# GPSTracker_v1_0.net
KiCad netlist of a schematic drawn in EAGLE
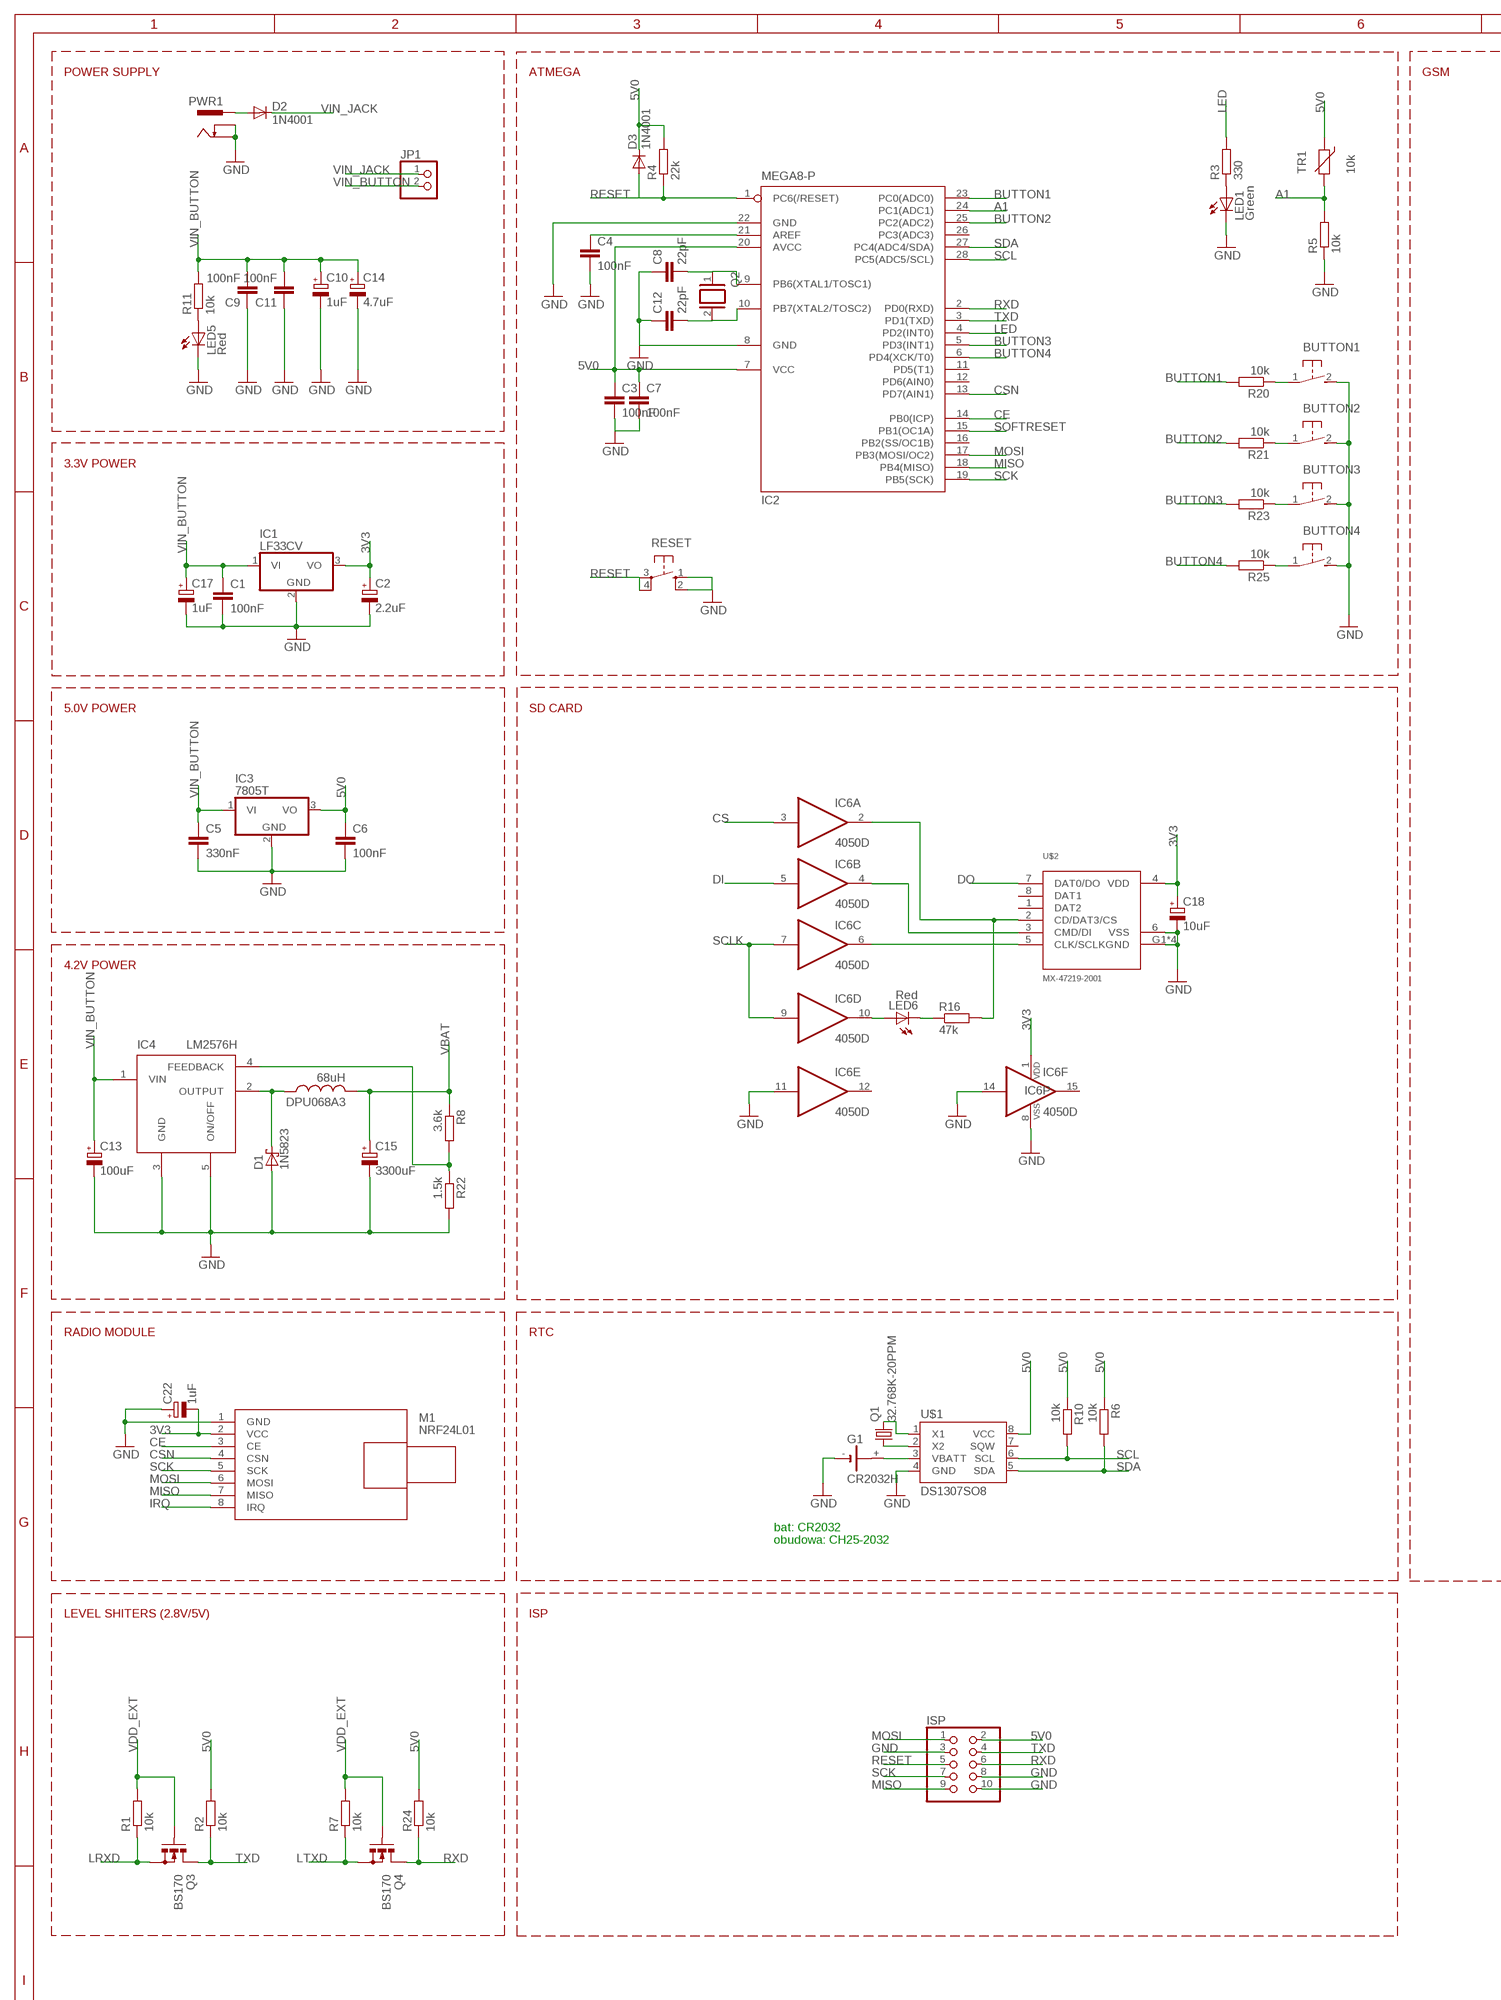
[diagram p0: schematic, sheet 1, part 1 of 2]
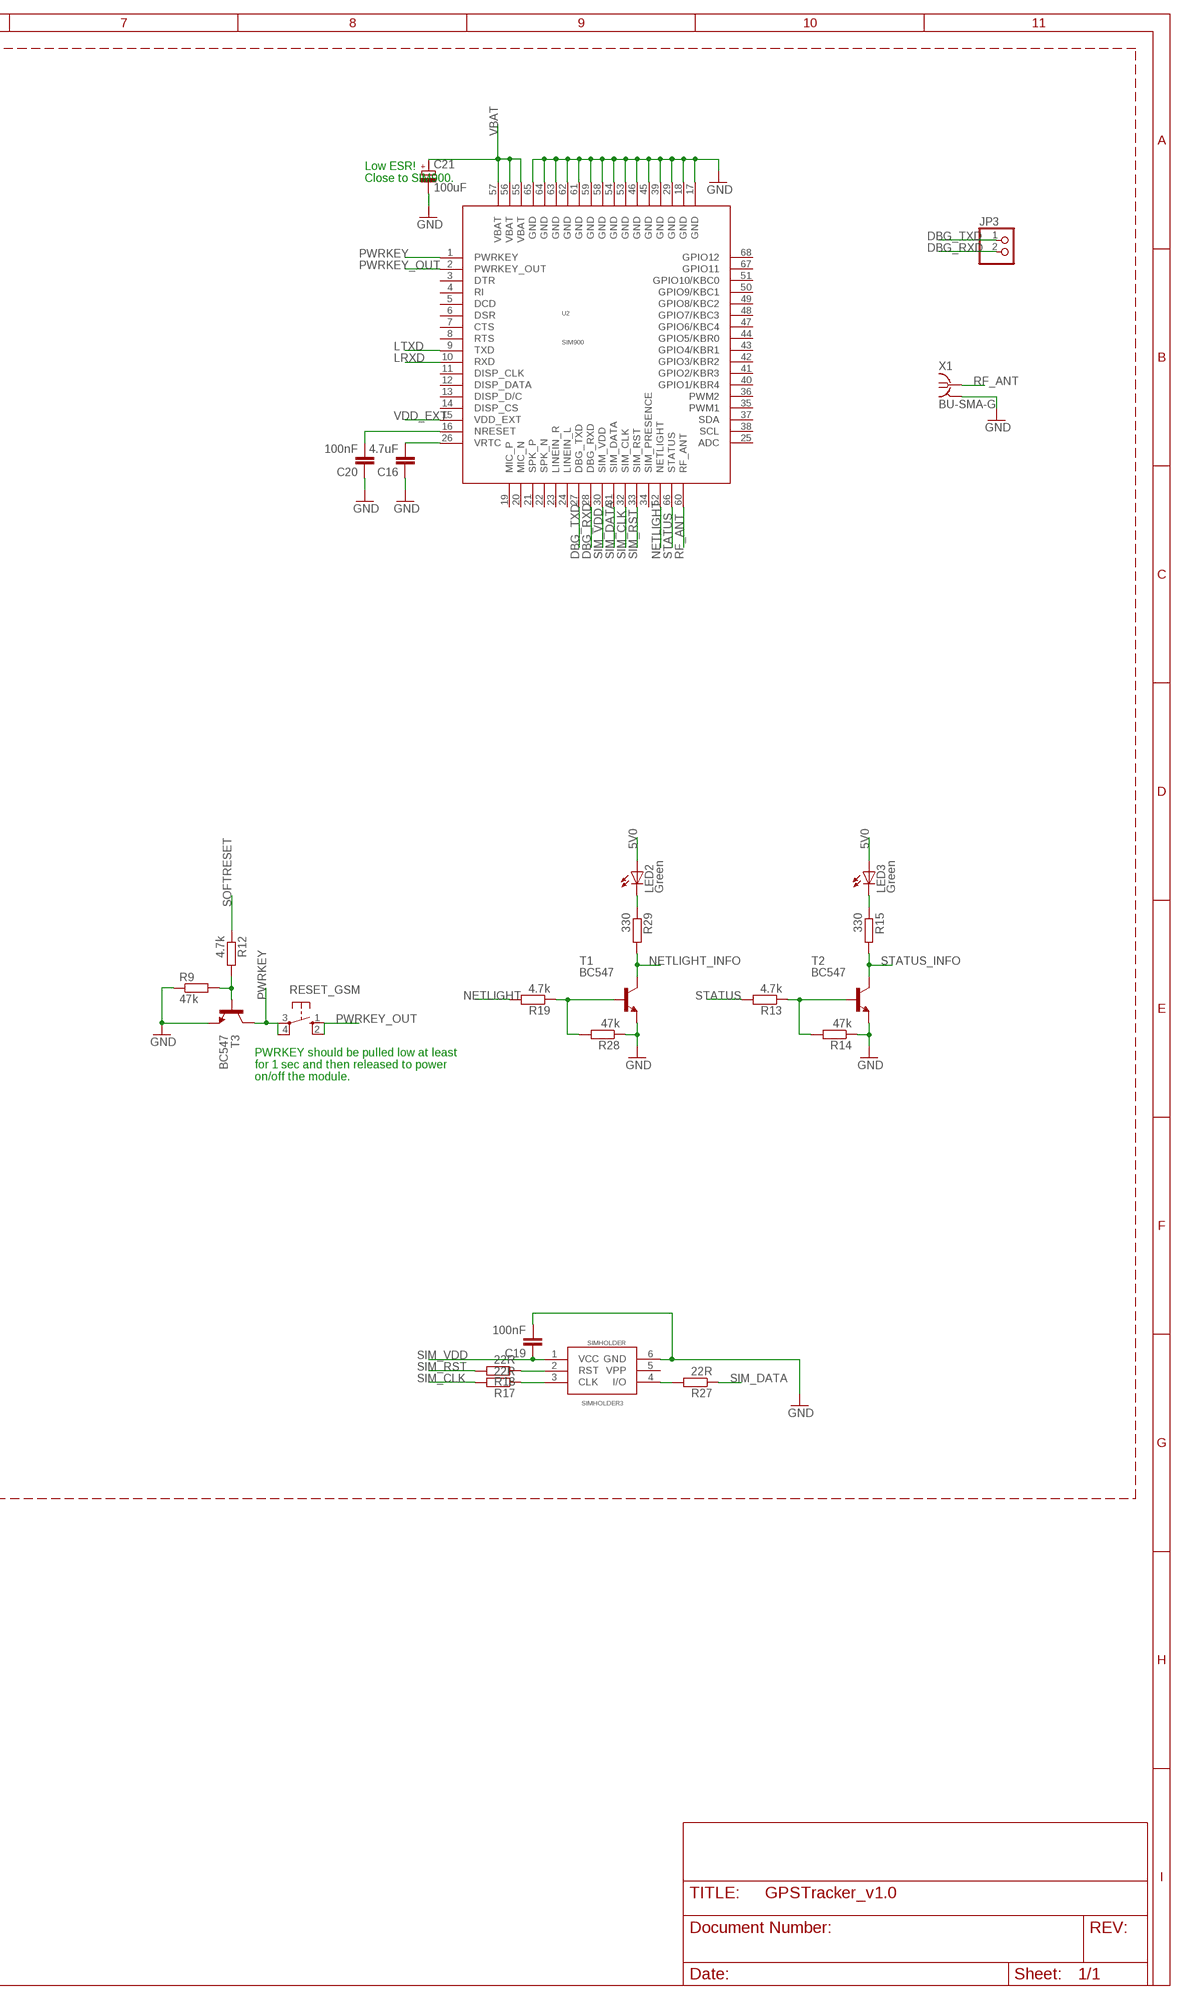
[diagram p1: schematic, sheet 1, part 2 of 2]

(export (version "E")
  (design (tool "Eeschema 10.0.6"))
  (components
    (comp (ref "BUTTON1")
      (value "31-XX")
      (footprint "eagle-import:B3F-31XX")
      (fields (field (name "MPN") "B3F-3100"))
      (libsource (lib "eagle-import") (part "31-XX"))
    )
    (comp (ref "BUTTON2")
      (value "31-XX")
      (footprint "eagle-import:B3F-31XX")
      (fields (field (name "MPN") "B3F-3100"))
      (libsource (lib "eagle-import") (part "31-XX"))
    )
    (comp (ref "BUTTON3")
      (value "31-XX")
      (footprint "eagle-import:B3F-31XX")
      (fields (field (name "MPN") "B3F-3100"))
      (libsource (lib "eagle-import") (part "31-XX"))
    )
    (comp (ref "BUTTON4")
      (value "31-XX")
      (footprint "eagle-import:B3F-31XX")
      (fields (field (name "MPN") "B3F-3100"))
      (libsource (lib "eagle-import") (part "31-XX"))
    )
    (comp (ref "C1")
      (value "100nF")
      (footprint "eagle-import:C025-025X050")
      (libsource (lib "eagle-import") (part "C-EU025-025X050"))
    )
    (comp (ref "C2")
      (value "2.2uF")
      (footprint "eagle-import:E2,5-5")
      (libsource (lib "eagle-import") (part "CPOL-EUE2.5-5"))
    )
    (comp (ref "C3")
      (value "100nF")
      (footprint "eagle-import:C025-025X050")
      (libsource (lib "eagle-import") (part "C-EU025-025X050"))
    )
    (comp (ref "C4")
      (value "100nF")
      (footprint "eagle-import:C025-025X050")
      (libsource (lib "eagle-import") (part "C-EU025-025X050"))
    )
    (comp (ref "C5")
      (value "330nF")
      (footprint "eagle-import:C025-025X050")
      (libsource (lib "eagle-import") (part "C-EU025-025X050"))
    )
    (comp (ref "C6")
      (value "100nF")
      (footprint "eagle-import:C025-025X050")
      (libsource (lib "eagle-import") (part "C-EU025-025X050"))
    )
    (comp (ref "C7")
      (value "100nF")
      (footprint "eagle-import:C025-025X050")
      (libsource (lib "eagle-import") (part "C-EU025-025X050"))
    )
    (comp (ref "C8")
      (value "22pF")
      (footprint "eagle-import:C025-025X050")
      (libsource (lib "eagle-import") (part "C-EU025-025X050"))
    )
    (comp (ref "C9")
      (value "100nF")
      (footprint "eagle-import:C025-025X050")
      (libsource (lib "eagle-import") (part "C-EU025-025X050"))
    )
    (comp (ref "C10")
      (value "1uF")
      (footprint "eagle-import:E2,5-5")
      (libsource (lib "eagle-import") (part "CPOL-EUE2.5-5"))
    )
    (comp (ref "C11")
      (value "100nF")
      (footprint "eagle-import:C025-025X050")
      (libsource (lib "eagle-import") (part "C-EU025-025X050"))
    )
    (comp (ref "C12")
      (value "22pF")
      (footprint "eagle-import:C025-025X050")
      (libsource (lib "eagle-import") (part "C-EU025-025X050"))
    )
    (comp (ref "C13")
      (value "100uF")
      (footprint "eagle-import:E2,5-5")
      (libsource (lib "eagle-import") (part "CPOL-EUE2.5-5"))
    )
    (comp (ref "C14")
      (value "4.7uF")
      (footprint "eagle-import:E2,5-5")
      (libsource (lib "eagle-import") (part "CPOL-EUE2.5-5"))
    )
    (comp (ref "C15")
      (value "3300uF")
      (footprint "eagle-import:E5-13")
      (libsource (lib "eagle-import") (part "CPOL-EUE5-13"))
    )
    (comp (ref "C16")
      (value "4.7uF")
      (footprint "eagle-import:C025-025X050")
      (libsource (lib "eagle-import") (part "C-EU025-025X050"))
    )
    (comp (ref "C17")
      (value "1uF")
      (footprint "eagle-import:E2,5-5")
      (libsource (lib "eagle-import") (part "CPOL-EUE2.5-5"))
    )
    (comp (ref "C18")
      (value "10uF")
      (footprint "eagle-import:E2,5-5")
      (libsource (lib "eagle-import") (part "CPOL-EUE2.5-5"))
    )
    (comp (ref "C19")
      (value "100nF")
      (footprint "eagle-import:C025-025X050")
      (libsource (lib "eagle-import") (part "C-EU025-025X050"))
    )
    (comp (ref "C20")
      (value "100nF")
      (footprint "eagle-import:C025-025X050")
      (libsource (lib "eagle-import") (part "C-EU025-025X050"))
    )
    (comp (ref "C21")
      (value "100uF")
      (footprint "eagle-import:E2,5-5")
      (libsource (lib "eagle-import") (part "CPOL-EUE2.5-5"))
    )
    (comp (ref "C22")
      (value "1uF")
      (footprint "eagle-import:E2,5-5")
      (libsource (lib "eagle-import") (part "CPOL-EUE2.5-5"))
    )
    (comp (ref "D1")
      (value "1N5823")
      (footprint "eagle-import:DO41-7.6")
      (libsource (lib "eagle-import") (part "1N5817-B"))
    )
    (comp (ref "D2")
      (value "1N4001")
      (footprint "eagle-import:DO41-10")
      (libsource (lib "eagle-import") (part "1N4004"))
    )
    (comp (ref "D3")
      (value "1N4001")
      (footprint "eagle-import:DO41-10")
      (libsource (lib "eagle-import") (part "1N4004"))
    )
    (comp (ref "DPU068A3")
      (value "68uH")
      (footprint "eagle-import:TJ4-U1")
      (libsource (lib "eagle-import") (part "L-USTJ4-U1"))
    )
    (comp (ref "G1")
      (value "CR2032H")
      (footprint "eagle-import:CR2032H")
      (libsource (lib "eagle-import") (part "CR2032H"))
    )
    (comp (ref "IC1")
      (value "LF33CV")
      (footprint "eagle-import:TO220H")
      (libsource (lib "eagle-import") (part "78T05"))
    )
    (comp (ref "IC2")
      (value "MEGA8-P")
      (footprint "eagle-import:DIL28-3")
      (libsource (lib "eagle-import") (part "MEGA8-P"))
    )
    (comp (ref "IC3")
      (value "7805T")
      (footprint "eagle-import:TO220H")
      (libsource (lib "eagle-import") (part "78T05"))
    )
    (comp (ref "IC4")
      (value "LM2576H")
      (footprint "eagle-import:TO220-52")
      (libsource (lib "eagle-import") (part "LM2576H"))
    )
    (comp (ref "IC6")
      (value "4050D")
      (footprint "eagle-import:SO16")
      (libsource (lib "eagle-import") (part "4050D"))
    )
    (comp (ref "ISP")
      (value "PINHD-2X5")
      (footprint "eagle-import:2X05")
      (libsource (lib "eagle-import") (part "PINHD-2X5"))
    )
    (comp (ref "JP1")
      (value "PINHD-1X2")
      (footprint "eagle-import:1X02")
      (libsource (lib "eagle-import") (part "PINHD-1X2"))
    )
    (comp (ref "JP3")
      (value "PINHD-1X2")
      (footprint "eagle-import:1X02")
      (libsource (lib "eagle-import") (part "PINHD-1X2"))
    )
    (comp (ref "LED1")
      (value "Green")
      (footprint "eagle-import:LED3MM")
      (libsource (lib "eagle-import") (part "LED3MM"))
    )
    (comp (ref "LED2")
      (value "Green")
      (footprint "eagle-import:LED3MM")
      (libsource (lib "eagle-import") (part "LED3MM"))
    )
    (comp (ref "LED3")
      (value "Green")
      (footprint "eagle-import:LED3MM")
      (libsource (lib "eagle-import") (part "LED3MM"))
    )
    (comp (ref "LED5")
      (value "Red")
      (footprint "eagle-import:LED3MM")
      (libsource (lib "eagle-import") (part "LED3MM"))
    )
    (comp (ref "LED6")
      (value "Red")
      (footprint "eagle-import:LED3MM")
      (libsource (lib "eagle-import") (part "LED3MM"))
    )
    (comp (ref "M1")
      (value "NRF24L01")
      (footprint "eagle-import:WIRELESS-NRD24L01-PA-EXT")
      (libsource (lib "eagle-import") (part "WIRELESS-NRF24L01-PA-EXT"))
    )
    (comp (ref "PWR1")
      (value "PWR-JAKPWR_JACK_UNI_MILLING")
      (footprint "eagle-import:PWR_JACK_UNI_MILLING")
      (libsource (lib "eagle-import") (part "PWR-JAKPWR_JACK_UNI_MILLING"))
    )
    (comp (ref "Q1")
      (value "32.768K-20PPM")
      (footprint "eagle-import:TC26V")
      (libsource (lib "eagle-import") (part "CRYSTALTC26V"))
    )
    (comp (ref "Q2")
      (value "XTAL/S")
      (footprint "eagle-import:QS")
      (libsource (lib "eagle-import") (part "XTAL/S"))
    )
    (comp (ref "Q3")
      (value "BS170")
      (footprint "eagle-import:SOT54E")
      (libsource (lib "eagle-import") (part "BS170"))
    )
    (comp (ref "Q4")
      (value "BS170")
      (footprint "eagle-import:SOT54E")
      (libsource (lib "eagle-import") (part "BS170"))
    )
    (comp (ref "R1")
      (value "10k")
      (footprint "eagle-import:0207_10")
      (libsource (lib "eagle-import") (part "R-EU_0207/10"))
    )
    (comp (ref "R2")
      (value "10k")
      (footprint "eagle-import:0207_10")
      (libsource (lib "eagle-import") (part "R-EU_0207/10"))
    )
    (comp (ref "R3")
      (value "330")
      (footprint "eagle-import:0207_10")
      (libsource (lib "eagle-import") (part "R-EU_0207/10"))
    )
    (comp (ref "R4")
      (value "22k")
      (footprint "eagle-import:0207_10")
      (libsource (lib "eagle-import") (part "R-EU_0207/10"))
    )
    (comp (ref "R5")
      (value "10k")
      (footprint "eagle-import:0207_10")
      (libsource (lib "eagle-import") (part "R-EU_0207/10"))
    )
    (comp (ref "R6")
      (value "10k")
      (footprint "eagle-import:0207_10")
      (libsource (lib "eagle-import") (part "R-EU_0207/10"))
    )
    (comp (ref "R7")
      (value "10k")
      (footprint "eagle-import:0207_10")
      (libsource (lib "eagle-import") (part "R-EU_0207/10"))
    )
    (comp (ref "R8")
      (value "3.6k")
      (footprint "eagle-import:0207_10")
      (libsource (lib "eagle-import") (part "R-EU_0207/10"))
    )
    (comp (ref "R9")
      (value "47k")
      (footprint "eagle-import:0207_10")
      (libsource (lib "eagle-import") (part "R-EU_0207/10"))
    )
    (comp (ref "R10")
      (value "10k")
      (footprint "eagle-import:0207_10")
      (libsource (lib "eagle-import") (part "R-EU_0207/10"))
    )
    (comp (ref "R11")
      (value "10k")
      (footprint "eagle-import:0207_10")
      (libsource (lib "eagle-import") (part "R-EU_0207/10"))
    )
    (comp (ref "R12")
      (value "4.7k")
      (footprint "eagle-import:0207_10")
      (libsource (lib "eagle-import") (part "R-EU_0207/10"))
    )
    (comp (ref "R13")
      (value "4.7k")
      (footprint "eagle-import:0207_10")
      (libsource (lib "eagle-import") (part "R-EU_0207/10"))
    )
    (comp (ref "R14")
      (value "47k")
      (footprint "eagle-import:0207_10")
      (libsource (lib "eagle-import") (part "R-EU_0207/10"))
    )
    (comp (ref "R15")
      (value "330")
      (footprint "eagle-import:0207_10")
      (libsource (lib "eagle-import") (part "R-EU_0207/10"))
    )
    (comp (ref "R16")
      (value "47k")
      (footprint "eagle-import:0207_10")
      (libsource (lib "eagle-import") (part "R-EU_0207/10"))
    )
    (comp (ref "R17")
      (value "22R")
      (footprint "eagle-import:0207_10")
      (libsource (lib "eagle-import") (part "R-EU_0207/10"))
    )
    (comp (ref "R18")
      (value "22R")
      (footprint "eagle-import:0207_10")
      (libsource (lib "eagle-import") (part "R-EU_0207/10"))
    )
    (comp (ref "R19")
      (value "4.7k")
      (footprint "eagle-import:0207_10")
      (libsource (lib "eagle-import") (part "R-EU_0207/10"))
    )
    (comp (ref "R20")
      (value "10k")
      (footprint "eagle-import:0207_10")
      (libsource (lib "eagle-import") (part "R-EU_0207/10"))
    )
    (comp (ref "R21")
      (value "10k")
      (footprint "eagle-import:0207_10")
      (libsource (lib "eagle-import") (part "R-EU_0207/10"))
    )
    (comp (ref "R22")
      (value "1.5k")
      (footprint "eagle-import:0207_10")
      (libsource (lib "eagle-import") (part "R-EU_0207/10"))
    )
    (comp (ref "R23")
      (value "10k")
      (footprint "eagle-import:0207_10")
      (libsource (lib "eagle-import") (part "R-EU_0207/10"))
    )
    (comp (ref "R24")
      (value "10k")
      (footprint "eagle-import:0207_10")
      (libsource (lib "eagle-import") (part "R-EU_0207/10"))
    )
    (comp (ref "R25")
      (value "10k")
      (footprint "eagle-import:0207_10")
      (libsource (lib "eagle-import") (part "R-EU_0207/10"))
    )
    (comp (ref "R27")
      (value "22R")
      (footprint "eagle-import:0207_10")
      (libsource (lib "eagle-import") (part "R-EU_0207/10"))
    )
    (comp (ref "R28")
      (value "47k")
      (footprint "eagle-import:0207_10")
      (libsource (lib "eagle-import") (part "R-EU_0207/10"))
    )
    (comp (ref "R29")
      (value "330")
      (footprint "eagle-import:0207_10")
      (libsource (lib "eagle-import") (part "R-EU_0207/10"))
    )
    (comp (ref "RESET")
      (value "10-XX")
      (footprint "eagle-import:B3F-10XX")
      (fields (field (name "MPN") "B3F-1000"))
      (libsource (lib "eagle-import") (part "10-XX"))
    )
    (comp (ref "RESET_GSM")
      (value "10-XX")
      (footprint "eagle-import:B3F-10XX")
      (fields (field (name "MPN") "B3F-1000"))
      (libsource (lib "eagle-import") (part "10-XX"))
    )
    (comp (ref "SIMHOLDER")
      (value "SIMHOLDER3")
      (footprint "eagle-import:SIMHOLDER3")
      (libsource (lib "eagle-import") (part "SIMHOLDER3"))
    )
    (comp (ref "T1")
      (value "BC547")
      (footprint "eagle-import:TO92")
      (libsource (lib "eagle-import") (part "BC547"))
    )
    (comp (ref "T2")
      (value "BC547")
      (footprint "eagle-import:TO92")
      (libsource (lib "eagle-import") (part "BC547"))
    )
    (comp (ref "T3")
      (value "BC547")
      (footprint "eagle-import:TO92")
      (libsource (lib "eagle-import") (part "BC547"))
    )
    (comp (ref "TR1")
      (value "10k")
      (footprint "eagle-import:RS-2,5")
      (libsource (lib "eagle-import") (part "THERMISTOR_R-2,5"))
    )
    (comp (ref "U$1")
      (value "DS1307SO8")
      (footprint "eagle-import:SO08")
      (libsource (lib "eagle-import") (part "DS1307SO8"))
    )
    (comp (ref "U$2")
      (value "MX-47219-2001")
      (footprint "eagle-import:MX-47219-2001")
      (libsource (lib "eagle-import") (part "MX-47219-2001"))
    )
    (comp (ref "U2")
      (value "SIM900")
      (footprint "eagle-import:SIM900")
      (libsource (lib "eagle-import") (part "SIM900"))
    )
    (comp (ref "X1")
      (value "BU-SMA-G")
      (footprint "eagle-import:BU-SMA-G")
      (libsource (lib "eagle-import") (part "BU-SMA-G"))
    )
  )
  (nets
    (net (code "1") (name "/3V3") (class "Default")
      (node (ref "C18") (pin "+") (pinfunction "+_+") (pintype "passive"))
      (node (ref "C2") (pin "+") (pinfunction "+_+") (pintype "passive"))
      (node (ref "C22") (pin "-") (pinfunction "-_-") (pintype "passive"))
      (node (ref "IC1") (pin "3") (pinfunction "VO_3") (pintype "passive"))
      (node (ref "IC6") (pin "1") (pinfunction "VDD_1") (pintype "power_in"))
      (node (ref "M1") (pin "2") (pinfunction "VCC_2") (pintype "power_in"))
      (node (ref "U$2") (pin "4") (pinfunction "VDD_4") (pintype "bidirectional"))
    )
    (net (code "2") (name "/5V0") (class "Default")
      (node (ref "C3") (pin "1") (pinfunction "1_1") (pintype "passive"))
      (node (ref "C6") (pin "1") (pinfunction "1_1") (pintype "passive"))
      (node (ref "C7") (pin "1") (pinfunction "1_1") (pintype "passive"))
      (node (ref "D3") (pin "C") (pinfunction "C_C") (pintype "passive"))
      (node (ref "IC2") (pin "20") (pinfunction "AVCC_20") (pintype "power_in"))
      (node (ref "IC2") (pin "7") (pinfunction "VCC_7") (pintype "power_in"))
      (node (ref "IC3") (pin "3") (pinfunction "VO_3") (pintype "passive"))
      (node (ref "ISP") (pin "2") (pinfunction "2_2") (pintype "passive"))
      (node (ref "LED2") (pin "A") (pinfunction "A_A") (pintype "passive"))
      (node (ref "LED3") (pin "A") (pinfunction "A_A") (pintype "passive"))
      (node (ref "R10") (pin "1") (pinfunction "1_1") (pintype "passive"))
      (node (ref "R2") (pin "2") (pinfunction "2_2") (pintype "passive"))
      (node (ref "R24") (pin "2") (pinfunction "2_2") (pintype "passive"))
      (node (ref "R4") (pin "2") (pinfunction "2_2") (pintype "passive"))
      (node (ref "R6") (pin "1") (pinfunction "1_1") (pintype "passive"))
      (node (ref "TR1") (pin "1") (pinfunction "1_1") (pintype "passive"))
      (node (ref "U$1") (pin "8") (pinfunction "VCC_8") (pintype "bidirectional"))
    )
    (net (code "3") (name "/A1") (class "Default")
      (node (ref "IC2") (pin "24") (pinfunction "PC1(ADC1)_24") (pintype "bidirectional"))
      (node (ref "R5") (pin "2") (pinfunction "2_2") (pintype "passive"))
      (node (ref "TR1") (pin "2") (pinfunction "2_2") (pintype "passive"))
    )
    (net (code "4") (name "/BUTTON1") (class "Default")
      (node (ref "IC2") (pin "23") (pinfunction "PC0(ADC0)_23") (pintype "bidirectional"))
      (node (ref "R20") (pin "2") (pinfunction "2_2") (pintype "passive"))
    )
    (net (code "5") (name "/BUTTON2") (class "Default")
      (node (ref "IC2") (pin "25") (pinfunction "PC2(ADC2)_25") (pintype "bidirectional"))
      (node (ref "R21") (pin "2") (pinfunction "2_2") (pintype "passive"))
    )
    (net (code "6") (name "/BUTTON3") (class "Default")
      (node (ref "IC2") (pin "5") (pinfunction "PD3(INT1)_5") (pintype "bidirectional"))
      (node (ref "R23") (pin "2") (pinfunction "2_2") (pintype "passive"))
    )
    (net (code "7") (name "/BUTTON4") (class "Default")
      (node (ref "IC2") (pin "6") (pinfunction "PD4(XCK/T0)_6") (pintype "bidirectional"))
      (node (ref "R25") (pin "2") (pinfunction "2_2") (pintype "passive"))
    )
    (net (code "8") (name "/CE") (class "Default")
      (node (ref "IC2") (pin "14") (pinfunction "PB0(ICP)_14") (pintype "bidirectional"))
      (node (ref "M1") (pin "3") (pinfunction "CE_3") (pintype "bidirectional"))
    )
    (net (code "9") (name "/CS") (class "Default")
      (node (ref "IC6") (pin "3") (pinfunction "I_3") (pintype "input"))
    )
    (net (code "10") (name "/CSN") (class "Default")
      (node (ref "IC2") (pin "13") (pinfunction "PD7(AIN1)_13") (pintype "bidirectional"))
      (node (ref "M1") (pin "4") (pinfunction "CSN_4") (pintype "bidirectional"))
    )
    (net (code "11") (name "/DBG_RXD") (class "Default")
      (node (ref "JP3") (pin "2") (pinfunction "2_2") (pintype "passive"))
      (node (ref "U2") (pin "28") (pinfunction "DBG_RXD_28") (pintype "input"))
    )
    (net (code "12") (name "/DBG_TXD") (class "Default")
      (node (ref "JP3") (pin "1") (pinfunction "1_1") (pintype "passive"))
      (node (ref "U2") (pin "27") (pinfunction "DBG_TXD_27") (pintype "output"))
    )
    (net (code "13") (name "/DI") (class "Default")
      (node (ref "IC6") (pin "5") (pinfunction "I_5") (pintype "input"))
    )
    (net (code "14") (name "/DO") (class "Default")
      (node (ref "U$2") (pin "7") (pinfunction "DAT0/DO_7") (pintype "bidirectional"))
    )
    (net (code "15") (name "/IRQ") (class "Default")
      (node (ref "M1") (pin "8") (pinfunction "IRQ_8") (pintype "bidirectional"))
    )
    (net (code "16") (name "/LED") (class "Default")
      (node (ref "IC2") (pin "4") (pinfunction "PD2(INT0)_4") (pintype "bidirectional"))
      (node (ref "R3") (pin "2") (pinfunction "2_2") (pintype "passive"))
    )
    (net (code "17") (name "/LRXD") (class "Default")
      (node (ref "Q3") (pin "S") (pinfunction "S_S") (pintype "passive"))
      (node (ref "R1") (pin "1") (pinfunction "1_1") (pintype "passive"))
      (node (ref "U2") (pin "10") (pinfunction "RXD_10") (pintype "input"))
    )
    (net (code "18") (name "/LTXD") (class "Default")
      (node (ref "Q4") (pin "S") (pinfunction "S_S") (pintype "passive"))
      (node (ref "R7") (pin "1") (pinfunction "1_1") (pintype "passive"))
      (node (ref "U2") (pin "9") (pinfunction "TXD_9") (pintype "output"))
    )
    (net (code "19") (name "/MISO") (class "Default")
      (node (ref "IC2") (pin "18") (pinfunction "PB4(MISO)_18") (pintype "bidirectional"))
      (node (ref "ISP") (pin "9") (pinfunction "9_9") (pintype "passive"))
      (node (ref "M1") (pin "7") (pinfunction "MISO_7") (pintype "bidirectional"))
    )
    (net (code "20") (name "/MOSI") (class "Default")
      (node (ref "IC2") (pin "17") (pinfunction "PB3(MOSI/OC2)_17") (pintype "bidirectional"))
      (node (ref "ISP") (pin "1") (pinfunction "1_1") (pintype "passive"))
      (node (ref "M1") (pin "6") (pinfunction "MOSI_6") (pintype "bidirectional"))
    )
    (net (code "21") (name "/NETLIGHT") (class "Default")
      (node (ref "R19") (pin "2") (pinfunction "2_2") (pintype "passive"))
      (node (ref "U2") (pin "52") (pinfunction "NETLIGHT_52") (pintype "output"))
    )
    (net (code "22") (name "/NETLIGHT_INFO") (class "Default")
      (node (ref "R29") (pin "2") (pinfunction "2_2") (pintype "passive"))
      (node (ref "T1") (pin "3") (pinfunction "C_3") (pintype "passive"))
    )
    (net (code "23") (name "/PWRKEY") (class "Default")
      (node (ref "RESET_GSM") (pin "3") (pinfunction "P_3") (pintype "passive"))
      (node (ref "RESET_GSM") (pin "4") (pinfunction "P1_4") (pintype "passive"))
      (node (ref "T3") (pin "3") (pinfunction "C_3") (pintype "passive"))
      (node (ref "U2") (pin "1") (pinfunction "PWRKEY_1") (pintype "input"))
    )
    (net (code "24") (name "/PWRKEY_OUT") (class "Default")
      (node (ref "RESET_GSM") (pin "1") (pinfunction "S_1") (pintype "passive"))
      (node (ref "RESET_GSM") (pin "2") (pinfunction "S1_2") (pintype "passive"))
      (node (ref "U2") (pin "2") (pinfunction "PWRKEY_OUT_2") (pintype "output"))
    )
    (net (code "25") (name "/RESET") (class "Default")
      (node (ref "D3") (pin "A") (pinfunction "A_A") (pintype "passive"))
      (node (ref "IC2") (pin "1") (pinfunction "PC6(/RESET)_1") (pintype "bidirectional"))
      (node (ref "ISP") (pin "5") (pinfunction "5_5") (pintype "passive"))
      (node (ref "R4") (pin "1") (pinfunction "1_1") (pintype "passive"))
      (node (ref "RESET") (pin "3") (pinfunction "P_3") (pintype "passive"))
      (node (ref "RESET") (pin "4") (pinfunction "P1_4") (pintype "passive"))
    )
    (net (code "26") (name "/RF_ANT") (class "Default")
      (node (ref "U2") (pin "60") (pinfunction "RF_ANT_60") (pintype "bidirectional"))
      (node (ref "X1") (pin "1") (pinfunction "1_1") (pintype "passive"))
    )
    (net (code "27") (name "/RXD") (class "Default")
      (node (ref "IC2") (pin "2") (pinfunction "PD0(RXD)_2") (pintype "bidirectional"))
      (node (ref "ISP") (pin "6") (pinfunction "6_6") (pintype "passive"))
      (node (ref "Q4") (pin "D") (pinfunction "D_D") (pintype "passive"))
      (node (ref "R24") (pin "1") (pinfunction "1_1") (pintype "passive"))
    )
    (net (code "28") (name "/SCK") (class "Default")
      (node (ref "IC2") (pin "19") (pinfunction "PB5(SCK)_19") (pintype "bidirectional"))
      (node (ref "ISP") (pin "7") (pinfunction "7_7") (pintype "passive"))
      (node (ref "M1") (pin "5") (pinfunction "SCK_5") (pintype "bidirectional"))
    )
    (net (code "29") (name "/SCL") (class "Default")
      (node (ref "IC2") (pin "28") (pinfunction "PC5(ADC5/SCL)_28") (pintype "bidirectional"))
      (node (ref "R10") (pin "2") (pinfunction "2_2") (pintype "passive"))
      (node (ref "U$1") (pin "6") (pinfunction "SCL_6") (pintype "bidirectional"))
    )
    (net (code "30") (name "/SCLK") (class "Default")
      (node (ref "IC6") (pin "7") (pinfunction "I_7") (pintype "input"))
      (node (ref "IC6") (pin "9") (pinfunction "I_9") (pintype "input"))
    )
    (net (code "31") (name "/SDA") (class "Default")
      (node (ref "IC2") (pin "27") (pinfunction "PC4(ADC4/SDA)_27") (pintype "bidirectional"))
      (node (ref "R6") (pin "2") (pinfunction "2_2") (pintype "passive"))
      (node (ref "U$1") (pin "5") (pinfunction "SDA_5") (pintype "bidirectional"))
    )
    (net (code "32") (name "/SIM_CLK") (class "Default")
      (node (ref "R17") (pin "2") (pinfunction "2_2") (pintype "passive"))
      (node (ref "U2") (pin "32") (pinfunction "SIM_CLK_32") (pintype "output"))
    )
    (net (code "33") (name "/SIM_DATA") (class "Default")
      (node (ref "R27") (pin "1") (pinfunction "1_1") (pintype "passive"))
      (node (ref "U2") (pin "31") (pinfunction "SIM_DATA_31") (pintype "bidirectional"))
    )
    (net (code "34") (name "/SIM_RST") (class "Default")
      (node (ref "R18") (pin "2") (pinfunction "2_2") (pintype "passive"))
      (node (ref "U2") (pin "33") (pinfunction "SIM_RST_33") (pintype "output"))
    )
    (net (code "35") (name "/SIM_VDD") (class "Default")
      (node (ref "C19") (pin "1") (pinfunction "1_1") (pintype "passive"))
      (node (ref "SIMHOLDER") (pin "1") (pinfunction "VCC_1") (pintype "bidirectional"))
      (node (ref "U2") (pin "30") (pinfunction "SIM_VDD_30") (pintype "output"))
    )
    (net (code "36") (name "/SOFTRESET") (class "Default")
      (node (ref "IC2") (pin "15") (pinfunction "PB1(OC1A)_15") (pintype "bidirectional"))
      (node (ref "R12") (pin "1") (pinfunction "1_1") (pintype "passive"))
    )
    (net (code "37") (name "/STATUS") (class "Default")
      (node (ref "R13") (pin "2") (pinfunction "2_2") (pintype "passive"))
      (node (ref "U2") (pin "66") (pinfunction "STATUS_66") (pintype "output"))
    )
    (net (code "38") (name "/STATUS_INFO") (class "Default")
      (node (ref "R15") (pin "2") (pinfunction "2_2") (pintype "passive"))
      (node (ref "T2") (pin "3") (pinfunction "C_3") (pintype "passive"))
    )
    (net (code "39") (name "/TXD") (class "Default")
      (node (ref "IC2") (pin "3") (pinfunction "PD1(TXD)_3") (pintype "bidirectional"))
      (node (ref "ISP") (pin "4") (pinfunction "4_4") (pintype "passive"))
      (node (ref "Q3") (pin "D") (pinfunction "D_D") (pintype "passive"))
      (node (ref "R2") (pin "1") (pinfunction "1_1") (pintype "passive"))
    )
    (net (code "40") (name "/VBAT") (class "Default")
      (node (ref "C15") (pin "+") (pinfunction "+_+") (pintype "passive"))
      (node (ref "C21") (pin "+") (pinfunction "+_+") (pintype "passive"))
      (node (ref "DPU068A3") (pin "2") (pinfunction "2_2") (pintype "passive"))
      (node (ref "R8") (pin "1") (pinfunction "1_1") (pintype "passive"))
      (node (ref "U2") (pin "55") (pinfunction "VBAT_55") (pintype "power_in"))
      (node (ref "U2") (pin "56") (pinfunction "VBAT_56") (pintype "power_in"))
      (node (ref "U2") (pin "57") (pinfunction "VBAT_57") (pintype "power_in"))
    )
    (net (code "41") (name "/VDD_EXT") (class "Default")
      (node (ref "Q3") (pin "G") (pinfunction "G_G") (pintype "passive"))
      (node (ref "Q4") (pin "G") (pinfunction "G_G") (pintype "passive"))
      (node (ref "R1") (pin "2") (pinfunction "2_2") (pintype "passive"))
      (node (ref "R7") (pin "2") (pinfunction "2_2") (pintype "passive"))
      (node (ref "U2") (pin "15") (pinfunction "VDD_EXT_15") (pintype "output"))
    )
    (net (code "42") (name "/VIN_BUTTON") (class "Default")
      (node (ref "C1") (pin "1") (pinfunction "1_1") (pintype "passive"))
      (node (ref "C10") (pin "+") (pinfunction "+_+") (pintype "passive"))
      (node (ref "C11") (pin "2") (pinfunction "2_2") (pintype "passive"))
      (node (ref "C13") (pin "+") (pinfunction "+_+") (pintype "passive"))
      (node (ref "C14") (pin "+") (pinfunction "+_+") (pintype "passive"))
      (node (ref "C17") (pin "+") (pinfunction "+_+") (pintype "passive"))
      (node (ref "C5") (pin "1") (pinfunction "1_1") (pintype "passive"))
      (node (ref "C9") (pin "2") (pinfunction "2_2") (pintype "passive"))
      (node (ref "IC1") (pin "1") (pinfunction "VI_1") (pintype "input"))
      (node (ref "IC3") (pin "1") (pinfunction "VI_1") (pintype "input"))
      (node (ref "IC4") (pin "1") (pinfunction "VIN_1") (pintype "input"))
      (node (ref "JP1") (pin "2") (pinfunction "2_2") (pintype "passive"))
      (node (ref "R11") (pin "2") (pinfunction "2_2") (pintype "passive"))
    )
    (net (code "43") (name "/VIN_JACK") (class "Default")
      (node (ref "D2") (pin "C") (pinfunction "C_C") (pintype "passive"))
      (node (ref "JP1") (pin "1") (pinfunction "1_1") (pintype "passive"))
    )
    (net (code "44") (name "GND") (class "Default")
      (node (ref "BUTTON1") (pin "2") (pinfunction "S_2") (pintype "passive"))
      (node (ref "BUTTON2") (pin "2") (pinfunction "S_2") (pintype "passive"))
      (node (ref "BUTTON3") (pin "2") (pinfunction "S_2") (pintype "passive"))
      (node (ref "BUTTON4") (pin "2") (pinfunction "S_2") (pintype "passive"))
      (node (ref "C1") (pin "2") (pinfunction "2_2") (pintype "passive"))
      (node (ref "C10") (pin "-") (pinfunction "-_-") (pintype "passive"))
      (node (ref "C11") (pin "1") (pinfunction "1_1") (pintype "passive"))
      (node (ref "C12") (pin "1") (pinfunction "1_1") (pintype "passive"))
      (node (ref "C13") (pin "-") (pinfunction "-_-") (pintype "passive"))
      (node (ref "C14") (pin "-") (pinfunction "-_-") (pintype "passive"))
      (node (ref "C15") (pin "-") (pinfunction "-_-") (pintype "passive"))
      (node (ref "C16") (pin "1") (pinfunction "1_1") (pintype "passive"))
      (node (ref "C17") (pin "-") (pinfunction "-_-") (pintype "passive"))
      (node (ref "C18") (pin "-") (pinfunction "-_-") (pintype "passive"))
      (node (ref "C19") (pin "2") (pinfunction "2_2") (pintype "passive"))
      (node (ref "C2") (pin "-") (pinfunction "-_-") (pintype "passive"))
      (node (ref "C20") (pin "1") (pinfunction "1_1") (pintype "passive"))
      (node (ref "C21") (pin "-") (pinfunction "-_-") (pintype "passive"))
      (node (ref "C22") (pin "+") (pinfunction "+_+") (pintype "passive"))
      (node (ref "C3") (pin "2") (pinfunction "2_2") (pintype "passive"))
      (node (ref "C4") (pin "2") (pinfunction "2_2") (pintype "passive"))
      (node (ref "C5") (pin "2") (pinfunction "2_2") (pintype "passive"))
      (node (ref "C6") (pin "2") (pinfunction "2_2") (pintype "passive"))
      (node (ref "C7") (pin "2") (pinfunction "2_2") (pintype "passive"))
      (node (ref "C8") (pin "1") (pinfunction "1_1") (pintype "passive"))
      (node (ref "C9") (pin "1") (pinfunction "1_1") (pintype "passive"))
      (node (ref "D1") (pin "A") (pinfunction "A_A") (pintype "passive"))
      (node (ref "G1") (pin "-") (pinfunction "-_-") (pintype "passive"))
      (node (ref "IC1") (pin "2") (pinfunction "GND_2") (pintype "passive"))
      (node (ref "IC2") (pin "22") (pinfunction "GND_22") (pintype "power_in"))
      (node (ref "IC2") (pin "8") (pinfunction "GND_8") (pintype "power_in"))
      (node (ref "IC3") (pin "2") (pinfunction "GND_2") (pintype "passive"))
      (node (ref "IC4") (pin "3") (pinfunction "GND_3") (pintype "power_in"))
      (node (ref "IC4") (pin "5") (pinfunction "ON/OFF_5") (pintype "bidirectional"))
      (node (ref "IC6") (pin "11") (pinfunction "I_11") (pintype "input"))
      (node (ref "IC6") (pin "14") (pinfunction "I_14") (pintype "input"))
      (node (ref "IC6") (pin "8") (pinfunction "VSS_8") (pintype "power_in"))
      (node (ref "ISP") (pin "10") (pinfunction "10_10") (pintype "passive"))
      (node (ref "ISP") (pin "3") (pinfunction "3_3") (pintype "passive"))
      (node (ref "ISP") (pin "8") (pinfunction "8_8") (pintype "passive"))
      (node (ref "LED1") (pin "K") (pinfunction "C_K") (pintype "passive"))
      (node (ref "LED5") (pin "K") (pinfunction "C_K") (pintype "passive"))
      (node (ref "M1") (pin "1") (pinfunction "GND_1") (pintype "power_in"))
      (node (ref "PWR1") (pin "-") (pinfunction "-_-") (pintype "passive"))
      (node (ref "PWR1") (pin "--") (pinfunction "--_--") (pintype "passive"))
      (node (ref "R14") (pin "1") (pinfunction "1_1") (pintype "passive"))
      (node (ref "R22") (pin "2") (pinfunction "2_2") (pintype "passive"))
      (node (ref "R28") (pin "1") (pinfunction "1_1") (pintype "passive"))
      (node (ref "R5") (pin "1") (pinfunction "1_1") (pintype "passive"))
      (node (ref "R9") (pin "1") (pinfunction "1_1") (pintype "passive"))
      (node (ref "RESET") (pin "1") (pinfunction "S_1") (pintype "passive"))
      (node (ref "RESET") (pin "2") (pinfunction "S1_2") (pintype "passive"))
      (node (ref "SIMHOLDER") (pin "6") (pinfunction "GND_6") (pintype "bidirectional"))
      (node (ref "T1") (pin "1") (pinfunction "E_1") (pintype "passive"))
      (node (ref "T2") (pin "1") (pinfunction "E_1") (pintype "passive"))
      (node (ref "T3") (pin "1") (pinfunction "E_1") (pintype "passive"))
      (node (ref "U$1") (pin "4") (pinfunction "GND_4") (pintype "bidirectional"))
      (node (ref "U$2") (pin "6") (pinfunction "VSS_6") (pintype "bidirectional"))
      (node (ref "U$2") (pin "G1") (pinfunction "GND_G1") (pintype "bidirectional"))
      (node (ref "U$2") (pin "G2") (pinfunction "GND_G2") (pintype "bidirectional"))
      (node (ref "U$2") (pin "G3") (pinfunction "GND_G3") (pintype "bidirectional"))
      (node (ref "U$2") (pin "G4") (pinfunction "GND_G4") (pintype "bidirectional"))
      (node (ref "U2") (pin "17") (pinfunction "GND_17") (pintype "power_in"))
      (node (ref "U2") (pin "18") (pinfunction "GND_18") (pintype "power_in"))
      (node (ref "U2") (pin "29") (pinfunction "GND_29") (pintype "power_in"))
      (node (ref "U2") (pin "39") (pinfunction "GND_39") (pintype "power_in"))
      (node (ref "U2") (pin "45") (pinfunction "GND_45") (pintype "power_in"))
      (node (ref "U2") (pin "46") (pinfunction "GND_46") (pintype "power_in"))
      (node (ref "U2") (pin "53") (pinfunction "GND_53") (pintype "power_in"))
      (node (ref "U2") (pin "54") (pinfunction "GND_54") (pintype "power_in"))
      (node (ref "U2") (pin "58") (pinfunction "GND_58") (pintype "power_in"))
      (node (ref "U2") (pin "59") (pinfunction "GND_59") (pintype "power_in"))
      (node (ref "U2") (pin "61") (pinfunction "GND_61") (pintype "power_in"))
      (node (ref "U2") (pin "62") (pinfunction "GND_62") (pintype "power_in"))
      (node (ref "U2") (pin "63") (pinfunction "GND_63") (pintype "power_in"))
      (node (ref "U2") (pin "64") (pinfunction "GND_64") (pintype "power_in"))
      (node (ref "U2") (pin "65") (pinfunction "GND_65") (pintype "power_in"))
      (node (ref "X1") (pin "2") (pinfunction "2_2") (pintype "passive"))
      (node (ref "X1") (pin "3") (pinfunction "2_3") (pintype "passive"))
      (node (ref "X1") (pin "4") (pinfunction "2_4") (pintype "passive"))
      (node (ref "X1") (pin "5") (pinfunction "2_5") (pintype "passive"))
    )
    (net (code "45") (name "Net-(BUTTON1-P)") (class "Default")
      (node (ref "BUTTON1") (pin "1") (pinfunction "P_1") (pintype "passive"))
      (node (ref "R20") (pin "1") (pinfunction "1_1") (pintype "passive"))
    )
    (net (code "46") (name "Net-(BUTTON2-P)") (class "Default")
      (node (ref "BUTTON2") (pin "1") (pinfunction "P_1") (pintype "passive"))
      (node (ref "R21") (pin "1") (pinfunction "1_1") (pintype "passive"))
    )
    (net (code "47") (name "Net-(BUTTON3-P)") (class "Default")
      (node (ref "BUTTON3") (pin "1") (pinfunction "P_1") (pintype "passive"))
      (node (ref "R23") (pin "1") (pinfunction "1_1") (pintype "passive"))
    )
    (net (code "48") (name "Net-(BUTTON4-P)") (class "Default")
      (node (ref "BUTTON4") (pin "1") (pinfunction "P_1") (pintype "passive"))
      (node (ref "R25") (pin "1") (pinfunction "1_1") (pintype "passive"))
    )
    (net (code "49") (name "Net-(D2-PadA)") (class "Default")
      (node (ref "D2") (pin "A") (pinfunction "A_A") (pintype "passive"))
      (node (ref "PWR1") (pin "+") (pinfunction "+_+") (pintype "passive"))
    )
    (net (code "50") (name "Net-(IC2-AREF)") (class "Default")
      (node (ref "C4") (pin "1") (pinfunction "1_1") (pintype "passive"))
      (node (ref "IC2") (pin "21") (pinfunction "AREF_21") (pintype "passive"))
    )
    (net (code "51") (name "Net-(IC2-PB6(XTAL1{slash}TOSC1))") (class "Default")
      (node (ref "C8") (pin "2") (pinfunction "2_2") (pintype "passive"))
      (node (ref "IC2") (pin "9") (pinfunction "PB6(XTAL1/TOSC1)_9") (pintype "bidirectional"))
      (node (ref "Q2") (pin "1") (pinfunction "1_1") (pintype "passive"))
    )
    (net (code "52") (name "Net-(IC2-PB7(XTAL2{slash}TOSC2))") (class "Default")
      (node (ref "C12") (pin "2") (pinfunction "2_2") (pintype "passive"))
      (node (ref "IC2") (pin "10") (pinfunction "PB7(XTAL2/TOSC2)_10") (pintype "bidirectional"))
      (node (ref "Q2") (pin "2") (pinfunction "2_2") (pintype "passive"))
    )
    (net (code "53") (name "Net-(IC4-FEEDBACK)") (class "Default")
      (node (ref "IC4") (pin "4") (pinfunction "FEEDBACK_4") (pintype "bidirectional"))
      (node (ref "R22") (pin "1") (pinfunction "1_1") (pintype "passive"))
      (node (ref "R8") (pin "2") (pinfunction "2_2") (pintype "passive"))
    )
    (net (code "54") (name "Net-(IC4-OUTPUT)") (class "Default")
      (node (ref "D1") (pin "C") (pinfunction "C_C") (pintype "passive"))
      (node (ref "DPU068A3") (pin "1") (pinfunction "1_1") (pintype "passive"))
      (node (ref "IC4") (pin "2") (pinfunction "OUTPUT_2") (pintype "output"))
    )
    (net (code "55") (name "Net-(IC6A-O)") (class "Default")
      (node (ref "IC6") (pin "2") (pinfunction "O_2") (pintype "output"))
      (node (ref "R16") (pin "2") (pinfunction "2_2") (pintype "passive"))
      (node (ref "U$2") (pin "2") (pinfunction "CD/DAT3/CS_2") (pintype "bidirectional"))
    )
    (net (code "56") (name "Net-(IC6B-O)") (class "Default")
      (node (ref "IC6") (pin "4") (pinfunction "O_4") (pintype "output"))
      (node (ref "U$2") (pin "3") (pinfunction "CMD/DI_3") (pintype "bidirectional"))
    )
    (net (code "57") (name "Net-(IC6C-O)") (class "Default")
      (node (ref "IC6") (pin "6") (pinfunction "O_6") (pintype "output"))
      (node (ref "U$2") (pin "5") (pinfunction "CLK/SCLK_5") (pintype "bidirectional"))
    )
    (net (code "58") (name "Net-(IC6D-O)") (class "Default")
      (node (ref "IC6") (pin "10") (pinfunction "O_10") (pintype "output"))
      (node (ref "LED6") (pin "A") (pinfunction "A_A") (pintype "passive"))
    )
    (net (code "59") (name "Net-(LED1-PadA)") (class "Default")
      (node (ref "LED1") (pin "A") (pinfunction "A_A") (pintype "passive"))
      (node (ref "R3") (pin "1") (pinfunction "1_1") (pintype "passive"))
    )
    (net (code "60") (name "Net-(LED2-C)") (class "Default")
      (node (ref "LED2") (pin "K") (pinfunction "C_K") (pintype "passive"))
      (node (ref "R29") (pin "1") (pinfunction "1_1") (pintype "passive"))
    )
    (net (code "61") (name "Net-(LED3-C)") (class "Default")
      (node (ref "LED3") (pin "K") (pinfunction "C_K") (pintype "passive"))
      (node (ref "R15") (pin "1") (pinfunction "1_1") (pintype "passive"))
    )
    (net (code "62") (name "Net-(LED5-PadA)") (class "Default")
      (node (ref "LED5") (pin "A") (pinfunction "A_A") (pintype "passive"))
      (node (ref "R11") (pin "1") (pinfunction "1_1") (pintype "passive"))
    )
    (net (code "63") (name "Net-(LED6-C)") (class "Default")
      (node (ref "LED6") (pin "K") (pinfunction "C_K") (pintype "passive"))
      (node (ref "R16") (pin "1") (pinfunction "1_1") (pintype "passive"))
    )
    (net (code "64") (name "Net-(SIMHOLDER-CLK)") (class "Default")
      (node (ref "R17") (pin "1") (pinfunction "1_1") (pintype "passive"))
      (node (ref "SIMHOLDER") (pin "3") (pinfunction "CLK_3") (pintype "bidirectional"))
    )
    (net (code "65") (name "Net-(SIMHOLDER-I{slash}O)") (class "Default")
      (node (ref "R27") (pin "2") (pinfunction "2_2") (pintype "passive"))
      (node (ref "SIMHOLDER") (pin "4") (pinfunction "I/O_4") (pintype "bidirectional"))
    )
    (net (code "66") (name "Net-(SIMHOLDER-RST)") (class "Default")
      (node (ref "R18") (pin "1") (pinfunction "1_1") (pintype "passive"))
      (node (ref "SIMHOLDER") (pin "2") (pinfunction "RST_2") (pintype "bidirectional"))
    )
    (net (code "67") (name "Net-(T1-B)") (class "Default")
      (node (ref "R19") (pin "1") (pinfunction "1_1") (pintype "passive"))
      (node (ref "R28") (pin "2") (pinfunction "2_2") (pintype "passive"))
      (node (ref "T1") (pin "2") (pinfunction "B_2") (pintype "passive"))
    )
    (net (code "68") (name "Net-(T2-B)") (class "Default")
      (node (ref "R13") (pin "1") (pinfunction "1_1") (pintype "passive"))
      (node (ref "R14") (pin "2") (pinfunction "2_2") (pintype "passive"))
      (node (ref "T2") (pin "2") (pinfunction "B_2") (pintype "passive"))
    )
    (net (code "69") (name "Net-(T3-B)") (class "Default")
      (node (ref "R12") (pin "2") (pinfunction "2_2") (pintype "passive"))
      (node (ref "R9") (pin "2") (pinfunction "2_2") (pintype "passive"))
      (node (ref "T3") (pin "2") (pinfunction "B_2") (pintype "passive"))
    )
    (net (code "70") (name "Net-(U$1-VBATT)") (class "Default")
      (node (ref "G1") (pin "+") (pinfunction "+_+") (pintype "passive"))
      (node (ref "U$1") (pin "3") (pinfunction "VBATT_3") (pintype "bidirectional"))
    )
    (net (code "71") (name "Net-(U$1-X1)") (class "Default")
      (node (ref "Q1") (pin "2") (pinfunction "2_2") (pintype "passive"))
      (node (ref "U$1") (pin "1") (pinfunction "X1_1") (pintype "bidirectional"))
    )
    (net (code "72") (name "Net-(U$1-X2)") (class "Default")
      (node (ref "Q1") (pin "1") (pinfunction "1_1") (pintype "passive"))
      (node (ref "U$1") (pin "2") (pinfunction "X2_2") (pintype "bidirectional"))
    )
    (net (code "73") (name "Net-(U2-NRESET)") (class "Default")
      (node (ref "C20") (pin "2") (pinfunction "2_2") (pintype "passive"))
      (node (ref "U2") (pin "16") (pinfunction "NRESET_16") (pintype "input"))
    )
    (net (code "74") (name "Net-(U2-VRTC)") (class "Default")
      (node (ref "C16") (pin "2") (pinfunction "2_2") (pintype "passive"))
      (node (ref "U2") (pin "26") (pinfunction "VRTC_26") (pintype "bidirectional"))
    )
    (net (code "75") (name "unconnected-(IC2-PB2(SS{slash}OC1B)-Pad16)") (class "Default")
      (node (ref "IC2") (pin "16") (pinfunction "PB2(SS/OC1B)_16") (pintype "bidirectional"))
    )
    (net (code "76") (name "unconnected-(IC2-PC3(ADC3)-Pad26)") (class "Default")
      (node (ref "IC2") (pin "26") (pinfunction "PC3(ADC3)_26") (pintype "bidirectional"))
    )
    (net (code "77") (name "unconnected-(IC2-PD5(T1)-Pad11)") (class "Default")
      (node (ref "IC2") (pin "11") (pinfunction "PD5(T1)_11") (pintype "bidirectional"))
    )
    (net (code "78") (name "unconnected-(IC2-PD6(AIN0)-Pad12)") (class "Default")
      (node (ref "IC2") (pin "12") (pinfunction "PD6(AIN0)_12") (pintype "bidirectional"))
    )
    (net (code "79") (name "unconnected-(IC6E-O-Pad12)") (class "Default")
      (node (ref "IC6") (pin "12") (pinfunction "O_12") (pintype "output"))
    )
    (net (code "80") (name "unconnected-(IC6F-O-Pad15)") (class "Default")
      (node (ref "IC6") (pin "15") (pinfunction "O_15") (pintype "output"))
    )
    (net (code "81") (name "unconnected-(SIMHOLDER-VPP-Pad5)") (class "Default")
      (node (ref "SIMHOLDER") (pin "5") (pinfunction "VPP_5") (pintype "bidirectional"))
    )
    (net (code "82") (name "unconnected-(U$1-SQW-Pad7)") (class "Default")
      (node (ref "U$1") (pin "7") (pinfunction "SQW_7") (pintype "bidirectional"))
    )
    (net (code "83") (name "unconnected-(U$2-DAT1-Pad8)") (class "Default")
      (node (ref "U$2") (pin "8") (pinfunction "DAT1_8") (pintype "bidirectional"))
    )
    (net (code "84") (name "unconnected-(U$2-DAT2-Pad1)") (class "Default")
      (node (ref "U$2") (pin "1") (pinfunction "DAT2_1") (pintype "bidirectional"))
    )
    (net (code "85") (name "unconnected-(U2-ADC-Pad25)") (class "Default")
      (node (ref "U2") (pin "25") (pinfunction "ADC_25") (pintype "input"))
    )
    (net (code "86") (name "unconnected-(U2-CTS-Pad7)") (class "Default")
      (node (ref "U2") (pin "7") (pinfunction "CTS_7") (pintype "output"))
    )
    (net (code "87") (name "unconnected-(U2-DCD-Pad5)") (class "Default")
      (node (ref "U2") (pin "5") (pinfunction "DCD_5") (pintype "output"))
    )
    (net (code "88") (name "unconnected-(U2-DISP_CLK-Pad11)") (class "Default")
      (node (ref "U2") (pin "11") (pinfunction "DISP_CLK_11") (pintype "output"))
    )
    (net (code "89") (name "unconnected-(U2-DISP_CS-Pad14)") (class "Default")
      (node (ref "U2") (pin "14") (pinfunction "DISP_CS_14") (pintype "output"))
    )
    (net (code "90") (name "unconnected-(U2-DISP_DATA-Pad12)") (class "Default")
      (node (ref "U2") (pin "12") (pinfunction "DISP_DATA_12") (pintype "bidirectional"))
    )
    (net (code "91") (name "unconnected-(U2-DISP_D{slash}C-Pad13)") (class "Default")
      (node (ref "U2") (pin "13") (pinfunction "DISP_D/C_13") (pintype "output"))
    )
    (net (code "92") (name "unconnected-(U2-DSR-Pad6)") (class "Default")
      (node (ref "U2") (pin "6") (pinfunction "DSR_6") (pintype "output"))
    )
    (net (code "93") (name "unconnected-(U2-DTR-Pad3)") (class "Default")
      (node (ref "U2") (pin "3") (pinfunction "DTR_3") (pintype "input"))
    )
    (net (code "94") (name "unconnected-(U2-GPIO1{slash}KBR4-Pad40)") (class "Default")
      (node (ref "U2") (pin "40") (pinfunction "GPIO1/KBR4_40") (pintype "output"))
    )
    (net (code "95") (name "unconnected-(U2-GPIO2{slash}KBR3-Pad41)") (class "Default")
      (node (ref "U2") (pin "41") (pinfunction "GPIO2/KBR3_41") (pintype "output"))
    )
    (net (code "96") (name "unconnected-(U2-GPIO3{slash}KBR2-Pad42)") (class "Default")
      (node (ref "U2") (pin "42") (pinfunction "GPIO3/KBR2_42") (pintype "output"))
    )
    (net (code "97") (name "unconnected-(U2-GPIO4{slash}KBR1-Pad43)") (class "Default")
      (node (ref "U2") (pin "43") (pinfunction "GPIO4/KBR1_43") (pintype "output"))
    )
    (net (code "98") (name "unconnected-(U2-GPIO5{slash}KBR0-Pad44)") (class "Default")
      (node (ref "U2") (pin "44") (pinfunction "GPIO5/KBR0_44") (pintype "output"))
    )
    (net (code "99") (name "unconnected-(U2-GPIO6{slash}KBC4-Pad47)") (class "Default")
      (node (ref "U2") (pin "47") (pinfunction "GPIO6/KBC4_47") (pintype "input"))
    )
    (net (code "100") (name "unconnected-(U2-GPIO7{slash}KBC3-Pad48)") (class "Default")
      (node (ref "U2") (pin "48") (pinfunction "GPIO7/KBC3_48") (pintype "bidirectional"))
    )
    (net (code "101") (name "unconnected-(U2-GPIO8{slash}KBC2-Pad49)") (class "Default")
      (node (ref "U2") (pin "49") (pinfunction "GPIO8/KBC2_49") (pintype "input"))
    )
    (net (code "102") (name "unconnected-(U2-GPIO9{slash}KBC1-Pad50)") (class "Default")
      (node (ref "U2") (pin "50") (pinfunction "GPIO9/KBC1_50") (pintype "input"))
    )
    (net (code "103") (name "unconnected-(U2-GPIO10{slash}KBC0-Pad51)") (class "Default")
      (node (ref "U2") (pin "51") (pinfunction "GPIO10/KBC0_51") (pintype "bidirectional"))
    )
    (net (code "104") (name "unconnected-(U2-GPIO11-Pad67)") (class "Default")
      (node (ref "U2") (pin "67") (pinfunction "GPIO11_67") (pintype "bidirectional"))
    )
    (net (code "105") (name "unconnected-(U2-GPIO12-Pad68)") (class "Default")
      (node (ref "U2") (pin "68") (pinfunction "GPIO12_68") (pintype "bidirectional"))
    )
    (net (code "106") (name "unconnected-(U2-LINEIN_L-Pad24)") (class "Default")
      (node (ref "U2") (pin "24") (pinfunction "LINEIN_L_24") (pintype "input"))
    )
    (net (code "107") (name "unconnected-(U2-LINEIN_R-Pad23)") (class "Default")
      (node (ref "U2") (pin "23") (pinfunction "LINEIN_R_23") (pintype "input"))
    )
    (net (code "108") (name "unconnected-(U2-MIC_N-Pad20)") (class "Default")
      (node (ref "U2") (pin "20") (pinfunction "MIC_N_20") (pintype "input"))
    )
    (net (code "109") (name "unconnected-(U2-MIC_P-Pad19)") (class "Default")
      (node (ref "U2") (pin "19") (pinfunction "MIC_P_19") (pintype "input"))
    )
    (net (code "110") (name "unconnected-(U2-PWM1-Pad35)") (class "Default")
      (node (ref "U2") (pin "35") (pinfunction "PWM1_35") (pintype "output"))
    )
    (net (code "111") (name "unconnected-(U2-PWM2-Pad36)") (class "Default")
      (node (ref "U2") (pin "36") (pinfunction "PWM2_36") (pintype "output"))
    )
    (net (code "112") (name "unconnected-(U2-RI-Pad4)") (class "Default")
      (node (ref "U2") (pin "4") (pinfunction "RI_4") (pintype "output"))
    )
    (net (code "113") (name "unconnected-(U2-RTS-Pad8)") (class "Default")
      (node (ref "U2") (pin "8") (pinfunction "RTS_8") (pintype "input"))
    )
    (net (code "114") (name "unconnected-(U2-SCL-Pad38)") (class "Default")
      (node (ref "U2") (pin "38") (pinfunction "SCL_38") (pintype "output"))
    )
    (net (code "115") (name "unconnected-(U2-SDA-Pad37)") (class "Default")
      (node (ref "U2") (pin "37") (pinfunction "SDA_37") (pintype "bidirectional"))
    )
    (net (code "116") (name "unconnected-(U2-SIM_PRESENCE-Pad34)") (class "Default")
      (node (ref "U2") (pin "34") (pinfunction "SIM_PRESENCE_34") (pintype "input"))
    )
    (net (code "117") (name "unconnected-(U2-SPK_N-Pad22)") (class "Default")
      (node (ref "U2") (pin "22") (pinfunction "SPK_N_22") (pintype "output"))
    )
    (net (code "118") (name "unconnected-(U2-SPK_P-Pad21)") (class "Default")
      (node (ref "U2") (pin "21") (pinfunction "SPK_P_21") (pintype "output"))
    )
  )
)
